# ZHSD-JTAG.net
KiCad netlist of a schematic drawn in Altium Designer
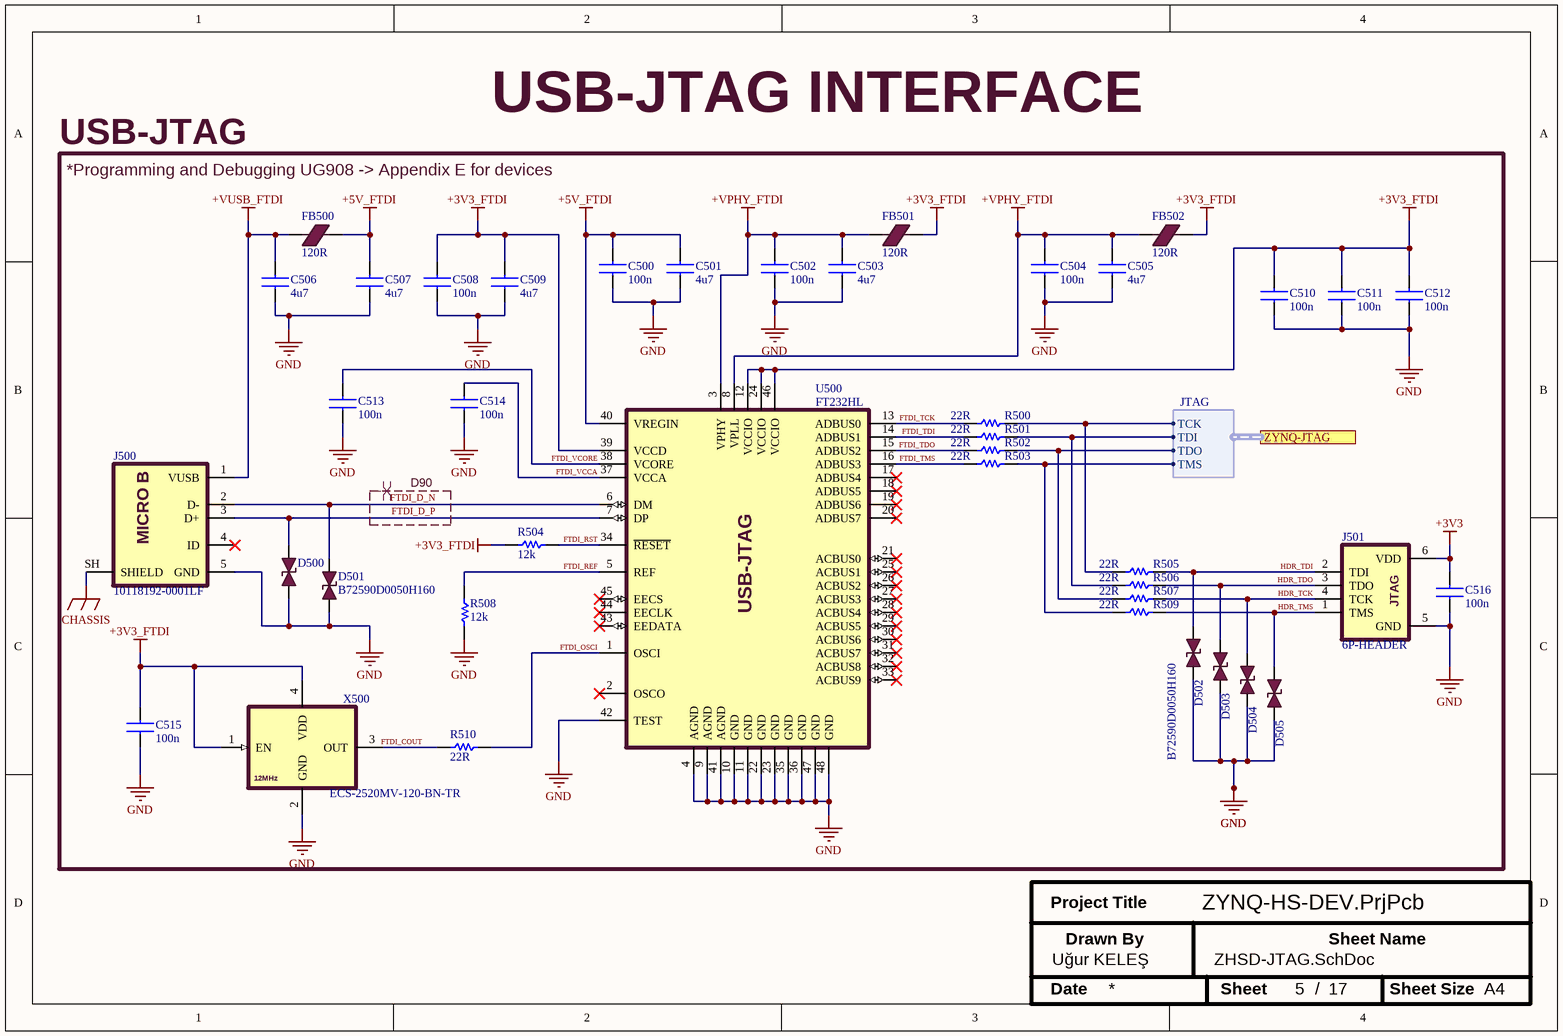
[diagram p0: ZHSD-JTAG.SchDoc]

(export (version "E")
  (design (tool "Eeschema 10.0.6"))
  (components
    (comp (ref "C500")
      (value "100n")
      (footprint "0603CAPC1608X09N")
      (description "CAP CER 0.1UF 16V X7R 0402 (1005) ±10%")
      (fields (field (name "MANUFACTURER") "Murata Electronics") (field (name "MPN") "GRM155R71C104KA88J"))
      (libsource (lib "UK_Library") (part "GRM155R71C104KA88J"))
    )
    (comp (ref "C501")
      (value "4u7")
      (footprint "0603CAPC1608X09N")
      (description "CAP CER 4.7UF 10V X5R 0603 (1608) ±10%")
      (fields
        (field (name "MANUFACTURER") "Samsung Electro-Mechanics")
        (field (name "MPN") "CL10A475KP8NNNC")
      )
      (libsource (lib "UK_Library") (part "CL10A475KP8NNNC"))
    )
    (comp (ref "C502")
      (value "100n")
      (footprint "0603CAPC1608X09N")
      (description "CAP CER 0.1UF 16V X7R 0402 (1005) ±10%")
      (fields (field (name "MANUFACTURER") "Murata Electronics") (field (name "MPN") "GRM155R71C104KA88J"))
      (libsource (lib "UK_Library") (part "GRM155R71C104KA88J"))
    )
    (comp (ref "C503")
      (value "4u7")
      (footprint "0603CAPC1608X09N")
      (description "CAP CER 4.7UF 10V X5R 0603 (1608) ±10%")
      (fields
        (field (name "MANUFACTURER") "Samsung Electro-Mechanics")
        (field (name "MPN") "CL10A475KP8NNNC")
      )
      (libsource (lib "UK_Library") (part "CL10A475KP8NNNC"))
    )
    (comp (ref "C504")
      (value "100n")
      (footprint "0603CAPC1608X09N")
      (description "CAP CER 0.1UF 16V X7R 0402 (1005) ±10%")
      (fields (field (name "MANUFACTURER") "Murata Electronics") (field (name "MPN") "GRM155R71C104KA88J"))
      (libsource (lib "UK_Library") (part "GRM155R71C104KA88J"))
    )
    (comp (ref "C505")
      (value "4u7")
      (footprint "0603CAPC1608X09N")
      (description "CAP CER 4.7UF 10V X5R 0603 (1608) ±10%")
      (fields
        (field (name "MANUFACTURER") "Samsung Electro-Mechanics")
        (field (name "MPN") "CL10A475KP8NNNC")
      )
      (libsource (lib "UK_Library") (part "CL10A475KP8NNNC"))
    )
    (comp (ref "C506")
      (value "4u7")
      (footprint "0603CAPC1608X09N")
      (description "CAP CER 4.7UF 10V X5R 0603 (1608) ±10%")
      (fields
        (field (name "MANUFACTURER") "Samsung Electro-Mechanics")
        (field (name "MPN") "CL10A475KP8NNNC")
      )
      (libsource (lib "UK_Library") (part "CL10A475KP8NNNC"))
    )
    (comp (ref "C507")
      (value "4u7")
      (footprint "0603CAPC1608X09N")
      (description "CAP CER 4.7UF 10V X5R 0603 (1608) ±10%")
      (fields
        (field (name "MANUFACTURER") "Samsung Electro-Mechanics")
        (field (name "MPN") "CL10A475KP8NNNC")
      )
      (libsource (lib "UK_Library") (part "CL10A475KP8NNNC"))
    )
    (comp (ref "C508")
      (value "100n")
      (footprint "0603CAPC1608X09N")
      (description "CAP CER 0.1UF 16V X7R 0402 (1005) ±10%")
      (fields (field (name "MANUFACTURER") "Murata Electronics") (field (name "MPN") "GRM155R71C104KA88J"))
      (libsource (lib "UK_Library") (part "GRM155R71C104KA88J"))
    )
    (comp (ref "C509")
      (value "4u7")
      (footprint "0603CAPC1608X09N")
      (description "CAP CER 4.7UF 10V X5R 0603 (1608) ±10%")
      (fields
        (field (name "MANUFACTURER") "Samsung Electro-Mechanics")
        (field (name "MPN") "CL10A475KP8NNNC")
      )
      (libsource (lib "UK_Library") (part "CL10A475KP8NNNC"))
    )
    (comp (ref "C510")
      (value "100n")
      (footprint "0603CAPC1608X09N")
      (description "CAP CER 0.1UF 16V X7R 0402 (1005) ±10%")
      (fields (field (name "MANUFACTURER") "Murata Electronics") (field (name "MPN") "GRM155R71C104KA88J"))
      (libsource (lib "UK_Library") (part "GRM155R71C104KA88J"))
    )
    (comp (ref "C511")
      (value "100n")
      (footprint "0603CAPC1608X09N")
      (description "CAP CER 0.1UF 16V X7R 0402 (1005) ±10%")
      (fields (field (name "MANUFACTURER") "Murata Electronics") (field (name "MPN") "GRM155R71C104KA88J"))
      (libsource (lib "UK_Library") (part "GRM155R71C104KA88J"))
    )
    (comp (ref "C512")
      (value "100n")
      (footprint "0603CAPC1608X09N")
      (description "CAP CER 0.1UF 16V X7R 0402 (1005) ±10%")
      (fields (field (name "MANUFACTURER") "Murata Electronics") (field (name "MPN") "GRM155R71C104KA88J"))
      (libsource (lib "UK_Library") (part "GRM155R71C104KA88J"))
    )
    (comp (ref "C513")
      (value "100n")
      (footprint "0603CAPC1608X09N")
      (description "CAP CER 0.1UF 16V X7R 0402 (1005) ±10%")
      (fields (field (name "MANUFACTURER") "Murata Electronics") (field (name "MPN") "GRM155R71C104KA88J"))
      (libsource (lib "UK_Library") (part "GRM155R71C104KA88J"))
    )
    (comp (ref "C514")
      (value "100n")
      (footprint "0603CAPC1608X09N")
      (description "CAP CER 0.1UF 16V X7R 0402 (1005) ±10%")
      (fields (field (name "MANUFACTURER") "Murata Electronics") (field (name "MPN") "GRM155R71C104KA88J"))
      (libsource (lib "UK_Library") (part "GRM155R71C104KA88J"))
    )
    (comp (ref "C515")
      (value "100n")
      (footprint "0603CAPC1608X09N")
      (description "CAP CER 0.1UF 16V X7R 0402 (1005) ±10%")
      (fields (field (name "MANUFACTURER") "Murata Electronics") (field (name "MPN") "GRM155R71C104KA88J"))
      (libsource (lib "UK_Library") (part "GRM155R71C104KA88J"))
    )
    (comp (ref "C516")
      (value "100n")
      (footprint "0603CAPC1608X09N")
      (description "CAP CER 0.1UF 16V X7R 0402 (1005) ±10%")
      (fields (field (name "MANUFACTURER") "Murata Electronics") (field (name "MPN") "GRM155R71C104KA88J"))
      (libsource (lib "UK_Library") (part "GRM155R71C104KA88J"))
    )
    (comp (ref "D500")
      (value "B72590D0050H160")
      (footprint "0402DIOC1005X06N")
      (description "Varistor 1 Circuit Surface Mount, MLCV 0402 (1005 Metric)")
      (fields (field (name "MANUFACTURER") "EPCOS - TDK Electronics"))
      (libsource (lib "UK_Library") (part "B72590D0050H160"))
    )
    (comp (ref "D501")
      (value "B72590D0050H160")
      (footprint "0402DIOC1005X06N")
      (description "Varistor 1 Circuit Surface Mount, MLCV 0402 (1005 Metric)")
      (fields (field (name "MANUFACTURER") "EPCOS - TDK Electronics"))
      (libsource (lib "UK_Library") (part "B72590D0050H160"))
    )
    (comp (ref "D502")
      (value "B72590D0050H160")
      (footprint "0402DIOC1005X06N")
      (description "Varistor 1 Circuit Surface Mount, MLCV 0402 (1005 Metric)")
      (fields (field (name "MANUFACTURER") "EPCOS - TDK Electronics"))
      (libsource (lib "UK_Library") (part "B72590D0050H160"))
    )
    (comp (ref "D503")
      (value "B72590D0050H160")
      (footprint "0402DIOC1005X06N")
      (description "Varistor 1 Circuit Surface Mount, MLCV 0402 (1005 Metric)")
      (fields (field (name "MANUFACTURER") "EPCOS - TDK Electronics"))
      (libsource (lib "UK_Library") (part "B72590D0050H160"))
    )
    (comp (ref "D504")
      (value "B72590D0050H160")
      (footprint "0402DIOC1005X06N")
      (description "Varistor 1 Circuit Surface Mount, MLCV 0402 (1005 Metric)")
      (fields (field (name "MANUFACTURER") "EPCOS - TDK Electronics"))
      (libsource (lib "UK_Library") (part "B72590D0050H160"))
    )
    (comp (ref "D505")
      (value "B72590D0050H160")
      (footprint "0402DIOC1005X06N")
      (description "Varistor 1 Circuit Surface Mount, MLCV 0402 (1005 Metric)")
      (fields (field (name "MANUFACTURER") "EPCOS - TDK Electronics"))
      (libsource (lib "UK_Library") (part "B72590D0050H160"))
    )
    (comp (ref "FB500")
      (value "120R")
      (footprint "0603INDC1608X08N")
      (description "FERRITE BEAD 120 OHM 0603 (1608) 3A 25mOhm")
      (fields (field (name "MANUFACTURER") "Murata Electronics") (field (name "MPN") "BLM18SG121TN1D"))
      (libsource (lib "UK_Library") (part "BLM18SG121TN1D"))
    )
    (comp (ref "FB501")
      (value "120R")
      (footprint "0603INDC1608X08N")
      (description "FERRITE BEAD 120 OHM 0603 (1608) 3A 25mOhm")
      (fields (field (name "MANUFACTURER") "Murata Electronics") (field (name "MPN") "BLM18SG121TN1D"))
      (libsource (lib "UK_Library") (part "BLM18SG121TN1D"))
    )
    (comp (ref "FB502")
      (value "120R")
      (footprint "0603INDC1608X08N")
      (description "FERRITE BEAD 120 OHM 0603 (1608) 3A 25mOhm")
      (fields (field (name "MANUFACTURER") "Murata Electronics") (field (name "MPN") "BLM18SG121TN1D"))
      (libsource (lib "UK_Library") (part "BLM18SG121TN1D"))
    )
    (comp (ref "J500")
      (value "10118192-0001LF")
      (footprint "USB2.0 MICRO B SMD")
      (description "CONN RCPT USB2.0 MICRO B SMD R/A")
      (fields (field (name "MANUFACTURER") "Amphenol ICC (FCI)"))
      (libsource (lib "UK_Library") (part "USB-MICRO-B"))
    )
    (comp (ref "J501")
      (value "6P-HEADER")
      (footprint "CONN-6P-HEADER")
      (description "JTAG CONN HEADER VERT 6POS 2.54MM")
      (libsource (lib "UK_Library") (part "JTAG-HEADER"))
    )
    (comp (ref "R500")
      (value "22R")
      (footprint "0603RESC1608X05N")
      (description "RES 22 OHM 1% 1/10W 0603 (1608)")
      (fields (field (name "MANUFACTURER") "YAGEO") (field (name "MPN") "RC0603FR-0722RL"))
      (libsource (lib "UK_Library") (part "RC0603FR-0722RL"))
    )
    (comp (ref "R501")
      (value "22R")
      (footprint "0603RESC1608X05N")
      (description "RES 22 OHM 1% 1/10W 0603 (1608)")
      (fields (field (name "MANUFACTURER") "YAGEO") (field (name "MPN") "RC0603FR-0722RL"))
      (libsource (lib "UK_Library") (part "RC0603FR-0722RL"))
    )
    (comp (ref "R502")
      (value "22R")
      (footprint "0603RESC1608X05N")
      (description "RES 22 OHM 1% 1/10W 0603 (1608)")
      (fields (field (name "MANUFACTURER") "YAGEO") (field (name "MPN") "RC0603FR-0722RL"))
      (libsource (lib "UK_Library") (part "RC0603FR-0722RL"))
    )
    (comp (ref "R503")
      (value "22R")
      (footprint "0603RESC1608X05N")
      (description "RES 22 OHM 1% 1/10W 0603 (1608)")
      (fields (field (name "MANUFACTURER") "YAGEO") (field (name "MPN") "RC0603FR-0722RL"))
      (libsource (lib "UK_Library") (part "RC0603FR-0722RL"))
    )
    (comp (ref "R504")
      (value "12k")
      (footprint "0603RESC1608X05N")
      (description "RES 12K OHM 1% 1/10W 0603 (1608)")
      (fields (field (name "MANUFACTURER") "YAGEO") (field (name "MPN") "RC0603FR-0712KL"))
      (libsource (lib "UK_Library") (part "RC0603FR-0712KL"))
    )
    (comp (ref "R505")
      (value "22R")
      (footprint "0603RESC1608X05N")
      (description "RES 22 OHM 1% 1/10W 0603 (1608)")
      (fields (field (name "MANUFACTURER") "YAGEO") (field (name "MPN") "RC0603FR-0722RL"))
      (libsource (lib "UK_Library") (part "RC0603FR-0722RL"))
    )
    (comp (ref "R506")
      (value "22R")
      (footprint "0603RESC1608X05N")
      (description "RES 22 OHM 1% 1/10W 0603 (1608)")
      (fields (field (name "MANUFACTURER") "YAGEO") (field (name "MPN") "RC0603FR-0722RL"))
      (libsource (lib "UK_Library") (part "RC0603FR-0722RL"))
    )
    (comp (ref "R507")
      (value "22R")
      (footprint "0603RESC1608X05N")
      (description "RES 22 OHM 1% 1/10W 0603 (1608)")
      (fields (field (name "MANUFACTURER") "YAGEO") (field (name "MPN") "RC0603FR-0722RL"))
      (libsource (lib "UK_Library") (part "RC0603FR-0722RL"))
    )
    (comp (ref "R508")
      (value "12k")
      (footprint "0603RESC1608X05N")
      (description "RES 12K OHM 1% 1/10W 0603 (1608)")
      (fields (field (name "MANUFACTURER") "YAGEO") (field (name "MPN") "RC0603FR-0712KL"))
      (libsource (lib "UK_Library") (part "RC0603FR-0712KL"))
    )
    (comp (ref "R509")
      (value "22R")
      (footprint "0603RESC1608X05N")
      (description "RES 22 OHM 1% 1/10W 0603 (1608)")
      (fields (field (name "MANUFACTURER") "YAGEO") (field (name "MPN") "RC0603FR-0722RL"))
      (libsource (lib "UK_Library") (part "RC0603FR-0722RL"))
    )
    (comp (ref "R510")
      (value "22R")
      (footprint "0603RESC1608X05N")
      (description "RES 22 OHM 1% 1/10W 0603 (1608)")
      (fields (field (name "MANUFACTURER") "YAGEO") (field (name "MPN") "RC0603FR-0722RL"))
      (libsource (lib "UK_Library") (part "RC0603FR-0722RL"))
    )
    (comp (ref "U500")
      (value "FT232HL")
      (footprint "LQFP50P900X900X160-48N")
      (description "USB Bridge, USB to UART (JTAG),FIFO USB 2.0 UART, FIFO Interface 48-LQFP (7x7)")
      (fields
        (field (name "MANUFACTURER") "FTDI, Future Technology Devices International Ltd")
        (field (name "MPN") "FT232HL-REEL")
      )
      (libsource (lib "UK_Library") (part "FT232HL"))
    )
    (comp (ref "X500")
      (value "ECS-2520MV-120-BN-TR")
      (footprint "XTAL_2520")
      (description "XTAL OSC XO 12.0000MHZ CMOS SMD")
      (fields (field (name "MANUFACTURER") "ECS Inc."))
      (libsource (lib "UK_Library") (part "ECS-2520MV-120-BN-TR"))
    )
  )
  (nets
    (net (code "2") (name "+3V3") (class "Default")
      (node (ref "C516") (pin "2") (pinfunction "2_2") (pintype "passive"))
      (node (ref "J501") (pin "6") (pinfunction "VDD_6") (pintype "passive"))
    )
    (net (code "3") (name "+3V3_FTDI") (class "Default")
      (node (ref "C508") (pin "2") (pinfunction "2_2") (pintype "passive"))
      (node (ref "C509") (pin "2") (pinfunction "2_2") (pintype "passive"))
      (node (ref "C510") (pin "2") (pinfunction "2_2") (pintype "passive"))
      (node (ref "C511") (pin "2") (pinfunction "2_2") (pintype "passive"))
      (node (ref "C512") (pin "2") (pinfunction "2_2") (pintype "passive"))
      (node (ref "C515") (pin "2") (pinfunction "2_2") (pintype "passive"))
      (node (ref "FB501") (pin "2") (pinfunction "2_2") (pintype "passive"))
      (node (ref "FB502") (pin "2") (pinfunction "2_2") (pintype "passive"))
      (node (ref "R504") (pin "1") (pinfunction "1_1") (pintype "passive"))
      (node (ref "U500") (pin "12") (pinfunction "VCCIO_12") (pintype "power_in"))
      (node (ref "U500") (pin "24") (pinfunction "VCCIO_24") (pintype "power_in"))
      (node (ref "U500") (pin "39") (pinfunction "VCCD_39") (pintype "power_in"))
      (node (ref "U500") (pin "46") (pinfunction "VCCIO_46") (pintype "power_in"))
      (node (ref "X500") (pin "1") (pinfunction "EN_1") (pintype "input"))
      (node (ref "X500") (pin "4") (pinfunction "VDD_4") (pintype "power_in"))
    )
    (net (code "4") (name "+5V_FTDI") (class "Default")
      (node (ref "C500") (pin "2") (pinfunction "2_2") (pintype "passive"))
      (node (ref "C501") (pin "2") (pinfunction "2_2") (pintype "passive"))
      (node (ref "C507") (pin "2") (pinfunction "2_2") (pintype "passive"))
      (node (ref "FB500") (pin "2") (pinfunction "2_2") (pintype "passive"))
      (node (ref "U500") (pin "40") (pinfunction "VREGIN_40") (pintype "power_in"))
    )
    (net (code "5") (name "+VPHY_FTDI") (class "Default")
      (node (ref "C502") (pin "2") (pinfunction "2_2") (pintype "passive"))
      (node (ref "C503") (pin "2") (pinfunction "2_2") (pintype "passive"))
      (node (ref "C504") (pin "2") (pinfunction "2_2") (pintype "passive"))
      (node (ref "C505") (pin "2") (pinfunction "2_2") (pintype "passive"))
      (node (ref "FB501") (pin "1") (pinfunction "1_1") (pintype "passive"))
      (node (ref "FB502") (pin "1") (pinfunction "1_1") (pintype "passive"))
      (node (ref "U500") (pin "3") (pinfunction "VPHY_3") (pintype "power_in"))
      (node (ref "U500") (pin "8") (pinfunction "VPLL_8") (pintype "power_in"))
    )
    (net (code "6") (name "+VUSB_FTDI") (class "Default")
      (node (ref "C506") (pin "2") (pinfunction "2_2") (pintype "passive"))
      (node (ref "FB500") (pin "1") (pinfunction "1_1") (pintype "passive"))
      (node (ref "J500") (pin "1") (pinfunction "VUSB_1") (pintype "passive"))
    )
    (net (code "7") (name "/FTDI_COUT") (class "Default")
      (node (ref "R510") (pin "1") (pinfunction "1_1") (pintype "passive"))
      (node (ref "X500") (pin "3") (pinfunction "OUT_3") (pintype "passive"))
    )
    (net (code "8") (name "/FTDI_D_N") (class "Default")
      (node (ref "D501") (pin "2") (pinfunction "2_2") (pintype "passive"))
      (node (ref "J500") (pin "2") (pinfunction "D-_2") (pintype "passive"))
      (node (ref "U500") (pin "6") (pinfunction "DM_6") (pintype "bidirectional"))
    )
    (net (code "9") (name "/FTDI_D_P") (class "Default")
      (node (ref "D500") (pin "2") (pinfunction "2_2") (pintype "passive"))
      (node (ref "J500") (pin "3") (pinfunction "D+_3") (pintype "passive"))
      (node (ref "U500") (pin "7") (pinfunction "DP_7") (pintype "bidirectional"))
    )
    (net (code "10") (name "/FTDI_OSCI") (class "Default")
      (node (ref "R510") (pin "2") (pinfunction "2_2") (pintype "passive"))
      (node (ref "U500") (pin "1") (pinfunction "OSCI_1") (pintype "passive"))
    )
    (net (code "11") (name "/FTDI_REF") (class "Default")
      (node (ref "R508") (pin "1") (pinfunction "1_1") (pintype "passive"))
      (node (ref "U500") (pin "5") (pinfunction "REF_5") (pintype "passive"))
    )
    (net (code "12") (name "/FTDI_RST") (class "Default")
      (node (ref "R504") (pin "2") (pinfunction "2_2") (pintype "passive"))
      (node (ref "U500") (pin "34") (pinfunction "RESET_34") (pintype "passive"))
    )
    (net (code "13") (name "/FTDI_TCK") (class "Default")
      (node (ref "R500") (pin "1") (pinfunction "1_1") (pintype "passive"))
      (node (ref "U500") (pin "13") (pinfunction "ADBUS0_13") (pintype "passive"))
    )
    (net (code "14") (name "/FTDI_TDI") (class "Default")
      (node (ref "R501") (pin "1") (pinfunction "1_1") (pintype "passive"))
      (node (ref "U500") (pin "14") (pinfunction "ADBUS1_14") (pintype "passive"))
    )
    (net (code "15") (name "/FTDI_TDO") (class "Default")
      (node (ref "R502") (pin "1") (pinfunction "1_1") (pintype "passive"))
      (node (ref "U500") (pin "15") (pinfunction "ADBUS2_15") (pintype "passive"))
    )
    (net (code "16") (name "/FTDI_TMS") (class "Default")
      (node (ref "R503") (pin "1") (pinfunction "1_1") (pintype "passive"))
      (node (ref "U500") (pin "16") (pinfunction "ADBUS3_16") (pintype "passive"))
    )
    (net (code "17") (name "/FTDI_VCCA") (class "Default")
      (node (ref "C514") (pin "2") (pinfunction "2_2") (pintype "passive"))
      (node (ref "U500") (pin "37") (pinfunction "VCCA_37") (pintype "power_in"))
    )
    (net (code "18") (name "/FTDI_VCORE") (class "Default")
      (node (ref "C513") (pin "2") (pinfunction "2_2") (pintype "passive"))
      (node (ref "U500") (pin "38") (pinfunction "VCORE_38") (pintype "power_in"))
    )
    (net (code "19") (name "/HDR_TCK") (class "Default")
      (node (ref "D504") (pin "2") (pinfunction "2_2") (pintype "passive"))
      (node (ref "J501") (pin "4") (pinfunction "TCK_4") (pintype "passive"))
      (node (ref "R507") (pin "2") (pinfunction "2_2") (pintype "passive"))
    )
    (net (code "20") (name "/HDR_TDI") (class "Default")
      (node (ref "D502") (pin "2") (pinfunction "2_2") (pintype "passive"))
      (node (ref "J501") (pin "2") (pinfunction "TDI_2") (pintype "passive"))
      (node (ref "R505") (pin "2") (pinfunction "2_2") (pintype "passive"))
    )
    (net (code "21") (name "/HDR_TDO") (class "Default")
      (node (ref "D503") (pin "2") (pinfunction "2_2") (pintype "passive"))
      (node (ref "J501") (pin "3") (pinfunction "TDO_3") (pintype "passive"))
      (node (ref "R506") (pin "2") (pinfunction "2_2") (pintype "passive"))
    )
    (net (code "22") (name "/HDR_TMS") (class "Default")
      (node (ref "D505") (pin "2") (pinfunction "2_2") (pintype "passive"))
      (node (ref "J501") (pin "1") (pinfunction "TMS_1") (pintype "passive"))
      (node (ref "R509") (pin "2") (pinfunction "2_2") (pintype "passive"))
    )
    (net (code "24") (name "CHASSIS") (class "Default")
      (node (ref "J500") (pin "SH") (pinfunction "SHIELD_SH") (pintype "passive"))
    )
    (net (code "25") (name "GND") (class "Default")
      (node (ref "C500") (pin "1") (pinfunction "1_1") (pintype "passive"))
      (node (ref "C501") (pin "1") (pinfunction "1_1") (pintype "passive"))
      (node (ref "C502") (pin "1") (pinfunction "1_1") (pintype "passive"))
      (node (ref "C503") (pin "1") (pinfunction "1_1") (pintype "passive"))
      (node (ref "C504") (pin "1") (pinfunction "1_1") (pintype "passive"))
      (node (ref "C505") (pin "1") (pinfunction "1_1") (pintype "passive"))
      (node (ref "C506") (pin "1") (pinfunction "1_1") (pintype "passive"))
      (node (ref "C507") (pin "1") (pinfunction "1_1") (pintype "passive"))
      (node (ref "C508") (pin "1") (pinfunction "1_1") (pintype "passive"))
      (node (ref "C509") (pin "1") (pinfunction "1_1") (pintype "passive"))
      (node (ref "C510") (pin "1") (pinfunction "1_1") (pintype "passive"))
      (node (ref "C511") (pin "1") (pinfunction "1_1") (pintype "passive"))
      (node (ref "C512") (pin "1") (pinfunction "1_1") (pintype "passive"))
      (node (ref "C513") (pin "1") (pinfunction "1_1") (pintype "passive"))
      (node (ref "C514") (pin "1") (pinfunction "1_1") (pintype "passive"))
      (node (ref "C515") (pin "1") (pinfunction "1_1") (pintype "passive"))
      (node (ref "C516") (pin "1") (pinfunction "1_1") (pintype "passive"))
      (node (ref "D500") (pin "1") (pinfunction "1_1") (pintype "passive"))
      (node (ref "D501") (pin "1") (pinfunction "1_1") (pintype "passive"))
      (node (ref "D502") (pin "1") (pinfunction "1_1") (pintype "passive"))
      (node (ref "D503") (pin "1") (pinfunction "1_1") (pintype "passive"))
      (node (ref "D504") (pin "1") (pinfunction "1_1") (pintype "passive"))
      (node (ref "D505") (pin "1") (pinfunction "1_1") (pintype "passive"))
      (node (ref "J500") (pin "5") (pinfunction "GND_5") (pintype "passive"))
      (node (ref "J501") (pin "5") (pinfunction "GND_5") (pintype "passive"))
      (node (ref "R508") (pin "2") (pinfunction "2_2") (pintype "passive"))
      (node (ref "U500") (pin "10") (pinfunction "GND_10") (pintype "power_in"))
      (node (ref "U500") (pin "11") (pinfunction "GND_11") (pintype "power_in"))
      (node (ref "U500") (pin "22") (pinfunction "GND_22") (pintype "power_in"))
      (node (ref "U500") (pin "23") (pinfunction "GND_23") (pintype "power_in"))
      (node (ref "U500") (pin "35") (pinfunction "GND_35") (pintype "power_in"))
      (node (ref "U500") (pin "36") (pinfunction "GND_36") (pintype "power_in"))
      (node (ref "U500") (pin "4") (pinfunction "AGND_4") (pintype "power_in"))
      (node (ref "U500") (pin "41") (pinfunction "AGND_41") (pintype "power_in"))
      (node (ref "U500") (pin "42") (pinfunction "TEST_42") (pintype "passive"))
      (node (ref "U500") (pin "47") (pinfunction "GND_47") (pintype "power_in"))
      (node (ref "U500") (pin "48") (pinfunction "GND_48") (pintype "power_in"))
      (node (ref "U500") (pin "9") (pinfunction "AGND_9") (pintype "power_in"))
      (node (ref "X500") (pin "2") (pinfunction "GND_2") (pintype "power_in"))
    )
    (net (code "26") (name "Net-(R500-Pad2)") (class "Default")
      (node (ref "R500") (pin "2") (pinfunction "2_2") (pintype "passive"))
      (node (ref "R505") (pin "1") (pinfunction "1_1") (pintype "passive"))
    )
    (net (code "27") (name "Net-(R501-Pad2)") (class "Default")
      (node (ref "R501") (pin "2") (pinfunction "2_2") (pintype "passive"))
      (node (ref "R506") (pin "1") (pinfunction "1_1") (pintype "passive"))
    )
    (net (code "28") (name "Net-(R502-Pad2)") (class "Default")
      (node (ref "R502") (pin "2") (pinfunction "2_2") (pintype "passive"))
      (node (ref "R507") (pin "1") (pinfunction "1_1") (pintype "passive"))
    )
    (net (code "29") (name "Net-(R503-Pad2)") (class "Default")
      (node (ref "R503") (pin "2") (pinfunction "2_2") (pintype "passive"))
      (node (ref "R509") (pin "1") (pinfunction "1_1") (pintype "passive"))
    )
    (net (code "30") (name "unconnected-(J500-ID-Pad4)") (class "Default")
      (node (ref "J500") (pin "4") (pinfunction "ID_4") (pintype "passive+no_connect"))
    )
    (net (code "31") (name "unconnected-(U500-ACBUS0-Pad21)") (class "Default")
      (node (ref "U500") (pin "21") (pinfunction "ACBUS0_21") (pintype "bidirectional+no_connect"))
    )
    (net (code "32") (name "unconnected-(U500-ACBUS1-Pad25)") (class "Default")
      (node (ref "U500") (pin "25") (pinfunction "ACBUS1_25") (pintype "bidirectional+no_connect"))
    )
    (net (code "33") (name "unconnected-(U500-ACBUS2-Pad26)") (class "Default")
      (node (ref "U500") (pin "26") (pinfunction "ACBUS2_26") (pintype "bidirectional+no_connect"))
    )
    (net (code "34") (name "unconnected-(U500-ACBUS3-Pad27)") (class "Default")
      (node (ref "U500") (pin "27") (pinfunction "ACBUS3_27") (pintype "bidirectional+no_connect"))
    )
    (net (code "35") (name "unconnected-(U500-ACBUS4-Pad28)") (class "Default")
      (node (ref "U500") (pin "28") (pinfunction "ACBUS4_28") (pintype "bidirectional+no_connect"))
    )
    (net (code "36") (name "unconnected-(U500-ACBUS5-Pad29)") (class "Default")
      (node (ref "U500") (pin "29") (pinfunction "ACBUS5_29") (pintype "bidirectional+no_connect"))
    )
    (net (code "37") (name "unconnected-(U500-ACBUS6-Pad30)") (class "Default")
      (node (ref "U500") (pin "30") (pinfunction "ACBUS6_30") (pintype "bidirectional+no_connect"))
    )
    (net (code "38") (name "unconnected-(U500-ACBUS7-Pad31)") (class "Default")
      (node (ref "U500") (pin "31") (pinfunction "ACBUS7_31") (pintype "bidirectional+no_connect"))
    )
    (net (code "39") (name "unconnected-(U500-ACBUS8-Pad32)") (class "Default")
      (node (ref "U500") (pin "32") (pinfunction "ACBUS8_32") (pintype "bidirectional+no_connect"))
    )
    (net (code "40") (name "unconnected-(U500-ACBUS9-Pad33)") (class "Default")
      (node (ref "U500") (pin "33") (pinfunction "ACBUS9_33") (pintype "bidirectional+no_connect"))
    )
    (net (code "41") (name "unconnected-(U500-ADBUS4-Pad17)") (class "Default")
      (node (ref "U500") (pin "17") (pinfunction "ADBUS4_17") (pintype "passive+no_connect"))
    )
    (net (code "42") (name "unconnected-(U500-ADBUS5-Pad18)") (class "Default")
      (node (ref "U500") (pin "18") (pinfunction "ADBUS5_18") (pintype "passive+no_connect"))
    )
    (net (code "43") (name "unconnected-(U500-ADBUS6-Pad19)") (class "Default")
      (node (ref "U500") (pin "19") (pinfunction "ADBUS6_19") (pintype "passive+no_connect"))
    )
    (net (code "44") (name "unconnected-(U500-ADBUS7-Pad20)") (class "Default")
      (node (ref "U500") (pin "20") (pinfunction "ADBUS7_20") (pintype "passive+no_connect"))
    )
    (net (code "45") (name "unconnected-(U500-EECLK-Pad44)") (class "Default")
      (node (ref "U500") (pin "44") (pinfunction "EECLK_44") (pintype "passive+no_connect"))
    )
    (net (code "46") (name "unconnected-(U500-EECS-Pad45)") (class "Default")
      (node (ref "U500") (pin "45") (pinfunction "EECS_45") (pintype "bidirectional+no_connect"))
    )
    (net (code "47") (name "unconnected-(U500-EEDATA-Pad43)") (class "Default")
      (node (ref "U500") (pin "43") (pinfunction "EEDATA_43") (pintype "bidirectional+no_connect"))
    )
    (net (code "48") (name "unconnected-(U500-OSCO-Pad2)") (class "Default")
      (node (ref "U500") (pin "2") (pinfunction "OSCO_2") (pintype "passive+no_connect"))
    )
  )
)
